# Motor_Drivers.net
KiCad netlist of a schematic drawn in Altium Designer
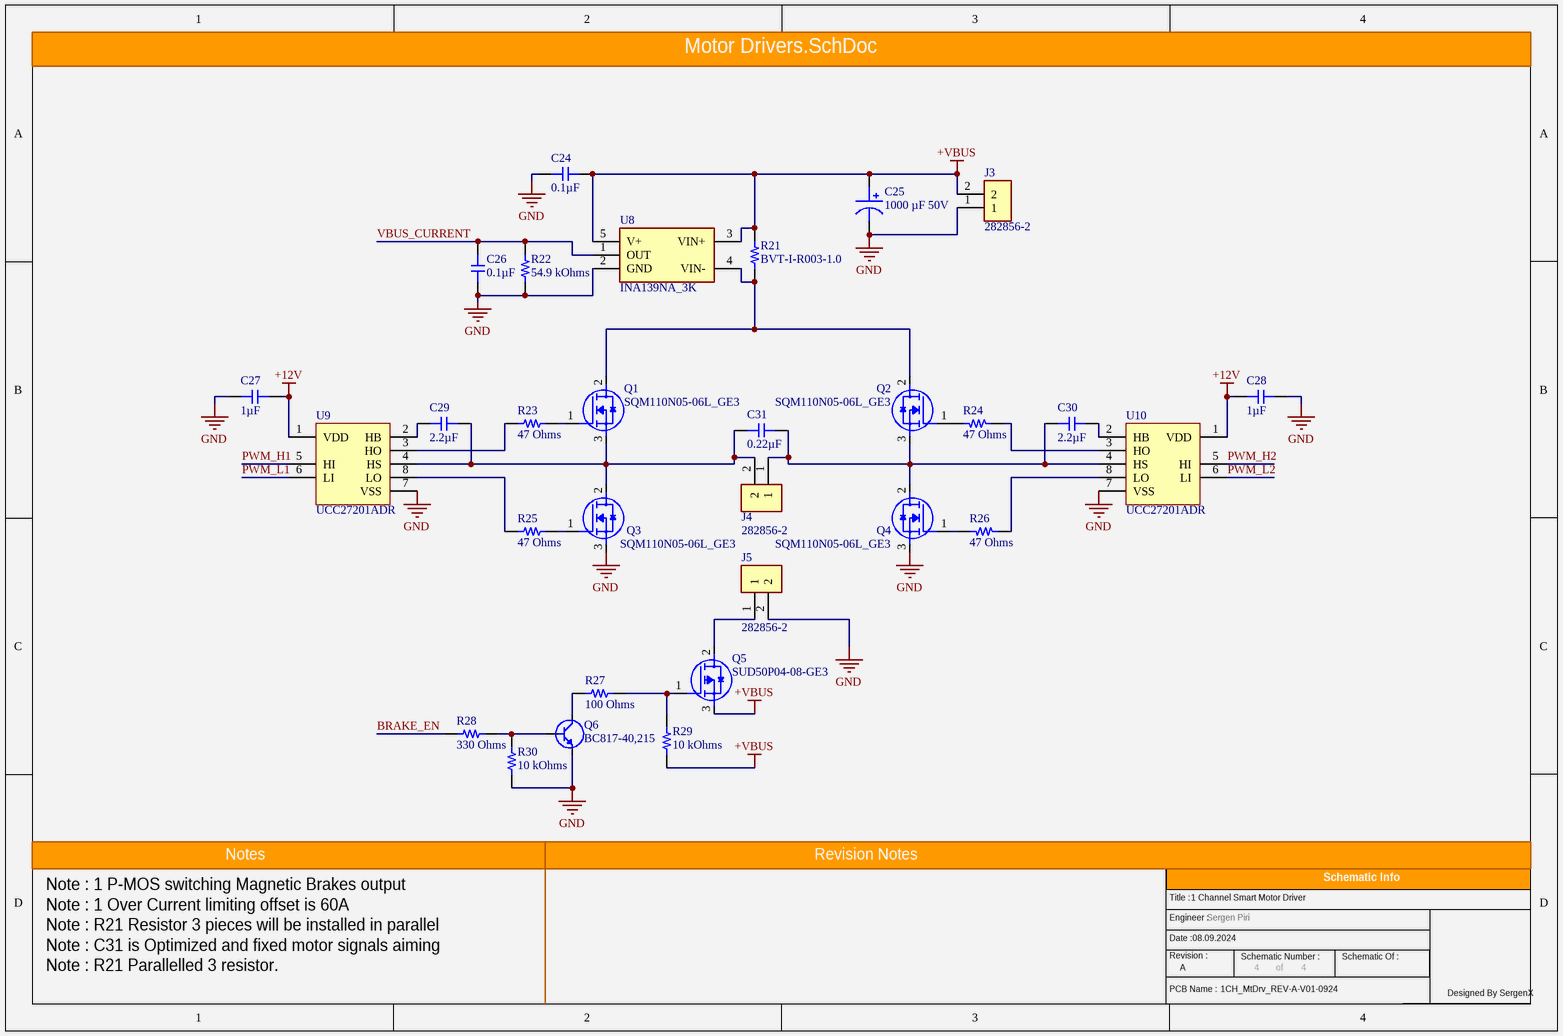
[diagram p0: Motor Drivers.SchDoc]

(export (version "E")
  (design (tool "Eeschema 10.0.6"))
  (components
    (comp (ref "C24")
      (value "0.1µF")
      (footprint "0603_Footprint")
      (description "0.1uF 0603 Surface Capacitor")
      (libsource (lib "MainLibrary") (part "0.1uF 0603 Surface Capacitor"))
    )
    (comp (ref "C25")
      (value "1000 µF 50V")
      (footprint "CAPPRD500W60D1250H2500")
      (description "1000礔 50V Aluminum Electrolytic Capacitors Radial, Can 2000 Hrs @ 85掳C")
      (libsource (lib "MainLibrary") (part "ECA1HM102"))
    )
    (comp (ref "C26")
      (value "0.1µF")
      (footprint "0603_Footprint")
      (description "0.1uF 0603 Surface Capacitor")
      (libsource (lib "MainLibrary") (part "0.1uF 0603 Surface Capacitor"))
    )
    (comp (ref "C27")
      (value "1µF")
      (footprint "0603_Footprint")
      (description "1uF 0603 Surface Capacitor")
      (libsource (lib "MainLibrary") (part "1uF 0603 Surface Capacitor"))
    )
    (comp (ref "C28")
      (value "1µF")
      (footprint "0603_Footprint")
      (description "1uF 0603 Surface Capacitor")
      (libsource (lib "MainLibrary") (part "1uF 0603 Surface Capacitor"))
    )
    (comp (ref "C29")
      (value "2.2µF")
      (footprint "0805")
      (description "2.2uF 0805 Surface Capacitor")
      (libsource (lib "MainLibrary") (part "2.2uF 0805 Surface Capacitor"))
    )
    (comp (ref "C30")
      (value "2.2µF")
      (footprint "0805")
      (description "2.2uF 0805 Surface Capacitor")
      (libsource (lib "MainLibrary") (part "2.2uF 0805 Surface Capacitor"))
    )
    (comp (ref "C31")
      (value "0.22µF")
      (footprint "0805")
      (description "0.22uF 0805 Surface Capacitor")
      (libsource (lib "MainLibrary") (part "0.22uF 0805 Surface Capacitor"))
    )
    (comp (ref "J3")
      (value "282856-2")
      (footprint "TE_282856-2")
      (description "TERMI-BLOK PCB MOUNT 2P")
      (fields (field (name "MF") "TE Connectivity"))
      (libsource (lib "") (part "282856-2_1"))
    )
    (comp (ref "J4")
      (value "282856-2")
      (footprint "TE_282856-2")
      (description "TERMI-BLOK PCB MOUNT 2P")
      (fields (field (name "MF") "TE Connectivity"))
      (libsource (lib "MainLibrary") (part "282856-2"))
    )
    (comp (ref "J5")
      (value "282856-2")
      (footprint "TE_282856-2")
      (description "TERMI-BLOK PCB MOUNT 2P")
      (fields (field (name "MF") "TE Connectivity"))
      (libsource (lib "") (part "282856-2_1"))
    )
    (comp (ref "Q1")
      (value "SQM110N05-06L_GE3")
      (footprint "DPAK254P1524X457-3N")
      (description "MOSFET DIS.110A 55V N-CH")
      (fields (field (name "MP") "IPB60R165CP") (field (name "MF") "Infineon"))
      (libsource (lib "MainLibrary") (part "SQM110N05-06L_GE3"))
    )
    (comp (ref "Q2")
      (value "SQM110N05-06L_GE3")
      (footprint "DPAK254P1524X457-3N")
      (description "MOSFET DIS.110A 55V N-CH")
      (fields (field (name "MP") "IPB60R165CP") (field (name "MF") "Infineon"))
      (libsource (lib "MainLibrary") (part "SQM110N05-06L_GE3"))
    )
    (comp (ref "Q3")
      (value "SQM110N05-06L_GE3")
      (footprint "DPAK254P1524X457-3N")
      (description "MOSFET DIS.110A 55V N-CH")
      (fields (field (name "MP") "IPB60R165CP") (field (name "MF") "Infineon"))
      (libsource (lib "MainLibrary") (part "SQM110N05-06L_GE3"))
    )
    (comp (ref "Q4")
      (value "SQM110N05-06L_GE3")
      (footprint "DPAK254P1524X457-3N")
      (description "MOSFET DIS.110A 55V N-CH")
      (fields (field (name "MP") "IPB60R165CP") (field (name "MF") "Infineon"))
      (libsource (lib "MainLibrary") (part "SQM110N05-06L_GE3"))
    )
    (comp (ref "Q5")
      (value "SUD50P04-08-GE3")
      (footprint "TO-252")
      (description "MOSFET (P-Channel) 50V 40A 8mOhms")
      (fields (field (name "MOUSER PART NUMBER") "781-SUD50P04-08-GE3"))
      (libsource (lib "MainLibrary") (part "SUD50P04-08-GE3"))
    )
    (comp (ref "Q6")
      (value "BC817-40,215")
      (footprint "BC81740215")
      (description "0.5A 45V BJT NPN Transistor SOT23 SMD")
      (fields (field (name "MOUSER PART NUMBER") "771-BC817-40-T/R"))
      (libsource (lib "MainLibrary") (part "BC817-40,215"))
    )
    (comp (ref "R21")
      (value "BVT-I-R003-1.0")
      (footprint "BVTIR00310")
      (description "3mOhm Resistor 2510 SMD Package")
      (libsource (lib "MainLibrary") (part "BVT-I-R003-1.0"))
    )
    (comp (ref "R22")
      (value "54.9 kOhms")
      (footprint "0603_RES")
      (description "54.9k Ohm 0603")
      (libsource (lib "MainLibrary") (part "54.9k Ohm 0603"))
    )
    (comp (ref "R23")
      (value "47 Ohms")
      (footprint "0603_RES")
      (description "47 Ohm 0603")
      (libsource (lib "MainLibrary") (part "47 Ohm 0603"))
    )
    (comp (ref "R24")
      (value "47 Ohms")
      (footprint "0603_RES")
      (description "47 Ohm 0603")
      (libsource (lib "MainLibrary") (part "47 Ohm 0603"))
    )
    (comp (ref "R25")
      (value "47 Ohms")
      (footprint "0603_RES")
      (description "47 Ohm 0603")
      (libsource (lib "MainLibrary") (part "47 Ohm 0603"))
    )
    (comp (ref "R26")
      (value "47 Ohms")
      (footprint "0603_RES")
      (description "47 Ohm 0603")
      (libsource (lib "MainLibrary") (part "47 Ohm 0603"))
    )
    (comp (ref "R27")
      (value "100 Ohms")
      (footprint "0603_RES")
      (description "100 Ohm 0603")
      (libsource (lib "MainLibrary") (part "100 Ohm 0603"))
    )
    (comp (ref "R28")
      (value "330 Ohms")
      (footprint "0603_RES")
      (description "330 Ohm 0603")
      (libsource (lib "MainLibrary") (part "330 Ohm 0603"))
    )
    (comp (ref "R29")
      (value "10 kOhms")
      (footprint "0603_RES")
      (description "10 kOhms 0603")
      (libsource (lib "MainLibrary") (part "10 kOhms 0603"))
    )
    (comp (ref "R30")
      (value "10 kOhms")
      (footprint "0603_RES")
      (description "10 kOhms 0603")
      (libsource (lib "MainLibrary") (part "10 kOhms 0603"))
    )
    (comp (ref "U8")
      (value "INA139NA_3K")
      (footprint "SOT95P280X145-5N")
      (description "%0.5 Current Monitor 60V Analog SMD")
      (fields
        (field (name "MANUFACTURER_PART_NUMBER") "INA139NA/3K")
        (field (name "MOUSER PART NUMBER") "595-INA139NA/3K")
      )
      (libsource (lib "MainLibrary") (part "INA139NA_3K"))
    )
    (comp (ref "U9")
      (value "UCC27201ADR")
      (footprint "MainLibrary:SOIC127P599X175-8N")
      (description "3-A, 120-V half bridge gate driver with 8-V UVLO and negative voltage handling")
      (fields (field (name "MF") "Texas Instruments"))
      (libsource (lib "MainLibrary") (part "UCC27201ADR"))
    )
    (comp (ref "U10")
      (value "UCC27201ADR")
      (footprint "MainLibrary:SOIC127P599X175-8N")
      (description "3-A, 120-V half bridge gate driver with 8-V UVLO and negative voltage handling")
      (fields (field (name "MF") "Texas Instruments"))
      (libsource (lib "") (part "UCC27201ADR_1"))
    )
  )
  (nets
    (net (code "1") (name "+12V") (class "Default")
      (node (ref "C27") (pin "2") (pinfunction "2_2") (pintype "passive"))
      (node (ref "C28") (pin "2") (pinfunction "2_2") (pintype "passive"))
      (node (ref "U10") (pin "1") (pinfunction "VDD_1") (pintype "passive"))
      (node (ref "U9") (pin "1") (pinfunction "VDD_1") (pintype "passive"))
    )
    (net (code "2") (name "+VBUS") (class "Default")
      (node (ref "C24") (pin "1") (pinfunction "1_1") (pintype "passive"))
      (node (ref "C25") (pin "P") (pinfunction "P_P") (pintype "passive"))
      (node (ref "J3") (pin "2") (pinfunction "2_2") (pintype "passive"))
      (node (ref "Q5") (pin "3") (pinfunction "S_3") (pintype "passive"))
      (node (ref "R21") (pin "2") (pinfunction "2_2") (pintype "passive"))
      (node (ref "R29") (pin "1") (pinfunction "1_1") (pintype "passive"))
      (node (ref "U8") (pin "3") (pinfunction "VIN+_3") (pintype "passive"))
      (node (ref "U8") (pin "5") (pinfunction "V+_5") (pintype "passive"))
    )
    (net (code "3") (name "/BRAKE_EN") (class "Default")
      (node (ref "R28") (pin "1") (pinfunction "1_1") (pintype "passive"))
    )
    (net (code "4") (name "/PWM_H1") (class "Default")
      (node (ref "U9") (pin "5") (pinfunction "HI_5") (pintype "passive"))
    )
    (net (code "5") (name "/PWM_H2") (class "Default")
      (node (ref "U10") (pin "5") (pinfunction "HI_5") (pintype "passive"))
    )
    (net (code "6") (name "/PWM_L1") (class "Default")
      (node (ref "U9") (pin "6") (pinfunction "LI_6") (pintype "passive"))
    )
    (net (code "7") (name "/PWM_L2") (class "Default")
      (node (ref "U10") (pin "6") (pinfunction "LI_6") (pintype "passive"))
    )
    (net (code "8") (name "/VBUS_CURRENT") (class "Default")
      (node (ref "C26") (pin "2") (pinfunction "2_2") (pintype "passive"))
      (node (ref "R22") (pin "2") (pinfunction "2_2") (pintype "passive"))
      (node (ref "U8") (pin "1") (pinfunction "OUT_1") (pintype "passive"))
    )
    (net (code "9") (name "GND") (class "Default")
      (node (ref "C24") (pin "2") (pinfunction "2_2") (pintype "passive"))
      (node (ref "C25") (pin "N") (pinfunction "N_N") (pintype "passive"))
      (node (ref "C26") (pin "1") (pinfunction "1_1") (pintype "passive"))
      (node (ref "C27") (pin "1") (pinfunction "1_1") (pintype "passive"))
      (node (ref "C28") (pin "1") (pinfunction "1_1") (pintype "passive"))
      (node (ref "J3") (pin "1") (pinfunction "1_1") (pintype "passive"))
      (node (ref "J5") (pin "2") (pinfunction "2_2") (pintype "passive"))
      (node (ref "Q3") (pin "3") (pinfunction "S_3") (pintype "passive"))
      (node (ref "Q4") (pin "3") (pinfunction "S_3") (pintype "passive"))
      (node (ref "Q6") (pin "2") (pinfunction "E_2") (pintype "passive"))
      (node (ref "R22") (pin "1") (pinfunction "1_1") (pintype "passive"))
      (node (ref "R30") (pin "2") (pinfunction "2_2") (pintype "passive"))
      (node (ref "U10") (pin "7") (pinfunction "VSS_7") (pintype "passive"))
      (node (ref "U8") (pin "2") (pinfunction "GND_2") (pintype "passive"))
      (node (ref "U9") (pin "7") (pinfunction "VSS_7") (pintype "passive"))
    )
    (net (code "10") (name "Net-(Q1-D)") (class "Default")
      (node (ref "Q1") (pin "2") (pinfunction "D_2") (pintype "passive"))
      (node (ref "Q2") (pin "2") (pinfunction "D_2") (pintype "passive"))
      (node (ref "R21") (pin "1") (pinfunction "1_1") (pintype "passive"))
      (node (ref "U8") (pin "4") (pinfunction "VIN-_4") (pintype "passive"))
    )
    (net (code "11") (name "Net-(Q1-G)") (class "Default")
      (node (ref "Q1") (pin "1") (pinfunction "G_1") (pintype "passive"))
      (node (ref "R23") (pin "2") (pinfunction "2_2") (pintype "passive"))
    )
    (net (code "12") (name "Net-(Q1-S)") (class "Default")
      (node (ref "C29") (pin "2") (pinfunction "2_2") (pintype "passive"))
      (node (ref "C31") (pin "1") (pinfunction "1_1") (pintype "passive"))
      (node (ref "J4") (pin "2") (pinfunction "2_2") (pintype "passive"))
      (node (ref "Q1") (pin "3") (pinfunction "S_3") (pintype "passive"))
      (node (ref "Q3") (pin "2") (pinfunction "D_2") (pintype "passive"))
      (node (ref "U9") (pin "4") (pinfunction "HS_4") (pintype "passive"))
    )
    (net (code "13") (name "Net-(Q2-G)") (class "Default")
      (node (ref "Q2") (pin "1") (pinfunction "G_1") (pintype "passive"))
      (node (ref "R24") (pin "2") (pinfunction "2_2") (pintype "passive"))
    )
    (net (code "14") (name "Net-(Q2-S)") (class "Default")
      (node (ref "C30") (pin "2") (pinfunction "2_2") (pintype "passive"))
      (node (ref "C31") (pin "2") (pinfunction "2_2") (pintype "passive"))
      (node (ref "J4") (pin "1") (pinfunction "1_1") (pintype "passive"))
      (node (ref "Q2") (pin "3") (pinfunction "S_3") (pintype "passive"))
      (node (ref "Q4") (pin "2") (pinfunction "D_2") (pintype "passive"))
      (node (ref "U10") (pin "4") (pinfunction "HS_4") (pintype "passive"))
    )
    (net (code "15") (name "Net-(Q3-G)") (class "Default")
      (node (ref "Q3") (pin "1") (pinfunction "G_1") (pintype "passive"))
      (node (ref "R25") (pin "2") (pinfunction "2_2") (pintype "passive"))
    )
    (net (code "16") (name "Net-(Q4-G)") (class "Default")
      (node (ref "Q4") (pin "1") (pinfunction "G_1") (pintype "passive"))
      (node (ref "R26") (pin "2") (pinfunction "2_2") (pintype "passive"))
    )
    (net (code "17") (name "Net-(Q5-D)") (class "Default")
      (node (ref "J5") (pin "1") (pinfunction "1_1") (pintype "passive"))
      (node (ref "Q5") (pin "2") (pinfunction "D_2") (pintype "passive"))
    )
    (net (code "18") (name "Net-(Q5-G)") (class "Default")
      (node (ref "Q5") (pin "1") (pinfunction "G_1") (pintype "passive"))
      (node (ref "R27") (pin "2") (pinfunction "2_2") (pintype "passive"))
      (node (ref "R29") (pin "2") (pinfunction "2_2") (pintype "passive"))
    )
    (net (code "19") (name "Net-(Q6-B)") (class "Default")
      (node (ref "Q6") (pin "1") (pinfunction "B_1") (pintype "passive"))
      (node (ref "R28") (pin "2") (pinfunction "2_2") (pintype "passive"))
      (node (ref "R30") (pin "1") (pinfunction "1_1") (pintype "passive"))
    )
    (net (code "20") (name "Net-(Q6-C)") (class "Default")
      (node (ref "Q6") (pin "3") (pinfunction "C_3") (pintype "passive"))
      (node (ref "R27") (pin "1") (pinfunction "1_1") (pintype "passive"))
    )
    (net (code "21") (name "Net-(U9-HB)") (class "Default")
      (node (ref "C29") (pin "1") (pinfunction "1_1") (pintype "passive"))
      (node (ref "U9") (pin "2") (pinfunction "HB_2") (pintype "passive"))
    )
    (net (code "22") (name "Net-(U9-HO)") (class "Default")
      (node (ref "R23") (pin "1") (pinfunction "1_1") (pintype "passive"))
      (node (ref "U9") (pin "3") (pinfunction "HO_3") (pintype "passive"))
    )
    (net (code "23") (name "Net-(U9-LO)") (class "Default")
      (node (ref "R25") (pin "1") (pinfunction "1_1") (pintype "passive"))
      (node (ref "U9") (pin "8") (pinfunction "LO_8") (pintype "passive"))
    )
    (net (code "24") (name "Net-(U10-HB)") (class "Default")
      (node (ref "C30") (pin "1") (pinfunction "1_1") (pintype "passive"))
      (node (ref "U10") (pin "2") (pinfunction "HB_2") (pintype "passive"))
    )
    (net (code "25") (name "Net-(U10-HO)") (class "Default")
      (node (ref "R24") (pin "1") (pinfunction "1_1") (pintype "passive"))
      (node (ref "U10") (pin "3") (pinfunction "HO_3") (pintype "passive"))
    )
    (net (code "26") (name "Net-(U10-LO)") (class "Default")
      (node (ref "R26") (pin "1") (pinfunction "1_1") (pintype "passive"))
      (node (ref "U10") (pin "8") (pinfunction "LO_8") (pintype "passive"))
    )
  )
)
